# ControlBoard.net
KiCad netlist of a schematic drawn in EAGLE
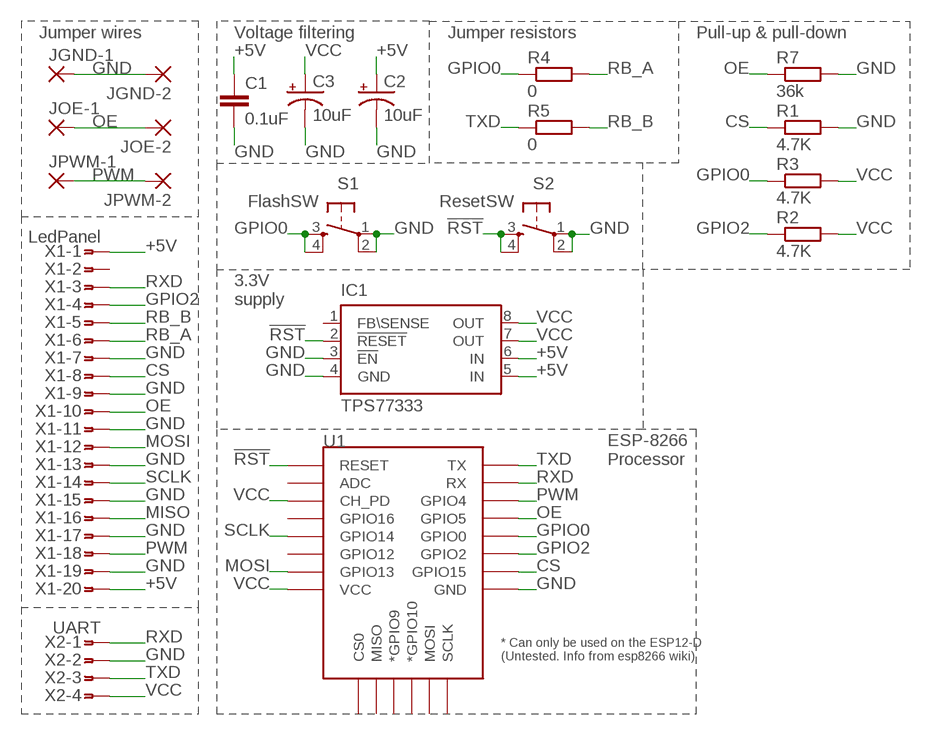
[diagram p0: schematic, sheet 1]

(export (version "E")
  (design (tool "Eeschema 10.0.6"))
  (components
    (comp (ref "C1")
      (value "0.1uF")
      (footprint "eagle-import:0603-CAP")
      (libsource (lib "eagle-import") (part "0.1UF-25V(+80/-20%)(0603)"))
    )
    (comp (ref "C2")
      (value "10uF")
      (footprint "eagle-import:EIA3528")
      (libsource (lib "eagle-import") (part "10UF-20V-10%(TANT)"))
    )
    (comp (ref "C3")
      (value "10uF")
      (footprint "eagle-import:EIA3528")
      (libsource (lib "eagle-import") (part "10UF-20V-10%(TANT)"))
    )
    (comp (ref "IC1")
      (value "TPS77333")
      (footprint "eagle-import:SOP-08")
      (fields (field (name "MF") "TEXAS INSTRUMENTS") (field (name "MPN") "TPS77333DGK"))
      (libsource (lib "eagle-import") (part "TPS77333"))
    )
    (comp (ref "JGND-1")
      (value "SMD2")
      (footprint "eagle-import:SMD1,27-2,54")
      (libsource (lib "eagle-import") (part "SMD2"))
    )
    (comp (ref "JGND-2")
      (value "SMD2")
      (footprint "eagle-import:SMD1,27-2,54")
      (libsource (lib "eagle-import") (part "SMD2"))
    )
    (comp (ref "JOE-1")
      (value "SMD2")
      (footprint "eagle-import:SMD1,27-2,54")
      (libsource (lib "eagle-import") (part "SMD2"))
    )
    (comp (ref "JOE-2")
      (value "SMD2")
      (footprint "eagle-import:SMD1,27-2,54")
      (libsource (lib "eagle-import") (part "SMD2"))
    )
    (comp (ref "JPWM-1")
      (value "SMD2")
      (footprint "eagle-import:SMD1,27-2,54")
      (libsource (lib "eagle-import") (part "SMD2"))
    )
    (comp (ref "JPWM-2")
      (value "SMD2")
      (footprint "eagle-import:SMD1,27-2,54")
      (libsource (lib "eagle-import") (part "SMD2"))
    )
    (comp (ref "R1")
      (value "4.7K")
      (footprint "eagle-import:R1206")
      (libsource (lib "eagle-import") (part "R-EU_R1206"))
    )
    (comp (ref "R2")
      (value "4.7K")
      (footprint "eagle-import:R1206")
      (libsource (lib "eagle-import") (part "R-EU_R1206"))
    )
    (comp (ref "R3")
      (value "4.7K")
      (footprint "eagle-import:R1206")
      (libsource (lib "eagle-import") (part "R-EU_R1206"))
    )
    (comp (ref "R4")
      (value "0")
      (footprint "eagle-import:R5025W")
      (libsource (lib "eagle-import") (part "R-EU_R5025W"))
    )
    (comp (ref "R5")
      (value "0")
      (footprint "eagle-import:R5025W")
      (libsource (lib "eagle-import") (part "R-EU_R5025W"))
    )
    (comp (ref "R7")
      (value "36k")
      (footprint "eagle-import:M2012")
      (libsource (lib "eagle-import") (part "R-EU_M2012"))
    )
    (comp (ref "S1")
      (value "FlashSW")
      (footprint "eagle-import:DTSM-6")
      (libsource (lib "eagle-import") (part "DTSM-6"))
    )
    (comp (ref "S2")
      (value "ResetSW")
      (footprint "eagle-import:DTSM-6")
      (libsource (lib "eagle-import") (part "DTSM-6"))
    )
    (comp (ref "U1")
      (value "ESP12ESMD")
      (footprint "eagle-import:ESP12E-SMD")
      (libsource (lib "eagle-import") (part "ESP12ESMD"))
    )
    (comp (ref "X1")
      (value "LedPanel")
      (footprint "eagle-import:SMDTOP20")
      (libsource (lib "eagle-import") (part "SMDTOP-20"))
    )
    (comp (ref "X2")
      (value "UART")
      (footprint "eagle-import:SMDTOP4")
      (libsource (lib "eagle-import") (part "SMDTOP-4"))
    )
  )
  (nets
    (net (code "1") (name "/+5V") (class "Default")
      (node (ref "C1") (pin "1") (pinfunction "1_1") (pintype "passive"))
      (node (ref "C2") (pin "A") (pinfunction "+_A") (pintype "passive"))
      (node (ref "IC1") (pin "5") (pinfunction "IN_5") (pintype "input"))
      (node (ref "IC1") (pin "6") (pinfunction "IN_6") (pintype "input"))
      (node (ref "X1") (pin "1") (pinfunction "1_1") (pintype "passive"))
      (node (ref "X1") (pin "20") (pinfunction "1_20") (pintype "passive"))
    )
    (net (code "2") (name "/CS") (class "Default")
      (node (ref "R1") (pin "1") (pinfunction "1_1") (pintype "passive"))
      (node (ref "U1") (pin "GPIO15") (pinfunction "GPIO15_GPIO15") (pintype "bidirectional"))
      (node (ref "X1") (pin "8") (pinfunction "1_8") (pintype "passive"))
    )
    (net (code "3") (name "/GND") (class "Default")
      (node (ref "C1") (pin "2") (pinfunction "2_2") (pintype "passive"))
      (node (ref "C2") (pin "C") (pinfunction "-_C") (pintype "passive"))
      (node (ref "C3") (pin "C") (pinfunction "-_C") (pintype "passive"))
      (node (ref "IC1") (pin "3") (pinfunction "~{EN}_3") (pintype "input"))
      (node (ref "IC1") (pin "4") (pinfunction "GND_4") (pintype "power_in"))
      (node (ref "JGND-1") (pin "1") (pinfunction "P_1") (pintype "passive"))
      (node (ref "JGND-2") (pin "1") (pinfunction "P_1") (pintype "passive"))
      (node (ref "R1") (pin "2") (pinfunction "2_2") (pintype "passive"))
      (node (ref "R7") (pin "2") (pinfunction "2_2") (pintype "passive"))
      (node (ref "S1") (pin "1") (pinfunction "1_1") (pintype "passive"))
      (node (ref "S1") (pin "2") (pinfunction "2_2") (pintype "passive"))
      (node (ref "S2") (pin "1") (pinfunction "1_1") (pintype "passive"))
      (node (ref "S2") (pin "2") (pinfunction "2_2") (pintype "passive"))
      (node (ref "U1") (pin "GND") (pinfunction "GND_GND") (pintype "bidirectional"))
      (node (ref "X1") (pin "11") (pinfunction "1_11") (pintype "passive"))
      (node (ref "X1") (pin "13") (pinfunction "1_13") (pintype "passive"))
      (node (ref "X1") (pin "15") (pinfunction "1_15") (pintype "passive"))
      (node (ref "X1") (pin "17") (pinfunction "1_17") (pintype "passive"))
      (node (ref "X1") (pin "19") (pinfunction "1_19") (pintype "passive"))
      (node (ref "X1") (pin "7") (pinfunction "1_7") (pintype "passive"))
      (node (ref "X1") (pin "9") (pinfunction "1_9") (pintype "passive"))
      (node (ref "X2") (pin "2") (pinfunction "1_2") (pintype "passive"))
    )
    (net (code "4") (name "/GPIO0") (class "Default")
      (node (ref "R3") (pin "1") (pinfunction "1_1") (pintype "passive"))
      (node (ref "R4") (pin "1") (pinfunction "1_1") (pintype "passive"))
      (node (ref "S1") (pin "3") (pinfunction "3_3") (pintype "passive"))
      (node (ref "S1") (pin "4") (pinfunction "4_4") (pintype "passive"))
      (node (ref "U1") (pin "GPIO0") (pinfunction "GPIO0_GPIO0") (pintype "bidirectional"))
    )
    (net (code "5") (name "/GPIO2") (class "Default")
      (node (ref "R2") (pin "1") (pinfunction "1_1") (pintype "passive"))
      (node (ref "U1") (pin "GPIO2") (pinfunction "GPIO2_GPIO2") (pintype "bidirectional"))
      (node (ref "X1") (pin "4") (pinfunction "1_4") (pintype "passive"))
    )
    (net (code "6") (name "/MISO") (class "Default")
      (node (ref "X1") (pin "16") (pinfunction "1_16") (pintype "passive"))
    )
    (net (code "7") (name "/MOSI") (class "Default")
      (node (ref "U1") (pin "GPIO13") (pinfunction "GPIO13_GPIO13") (pintype "bidirectional"))
      (node (ref "X1") (pin "12") (pinfunction "1_12") (pintype "passive"))
    )
    (net (code "8") (name "/OE") (class "Default")
      (node (ref "JOE-1") (pin "1") (pinfunction "P_1") (pintype "passive"))
      (node (ref "JOE-2") (pin "1") (pinfunction "P_1") (pintype "passive"))
      (node (ref "R7") (pin "1") (pinfunction "1_1") (pintype "passive"))
      (node (ref "U1") (pin "GPIO5") (pinfunction "GPIO5_GPIO5") (pintype "bidirectional"))
      (node (ref "X1") (pin "10") (pinfunction "1_10") (pintype "passive"))
    )
    (net (code "9") (name "/PWM") (class "Default")
      (node (ref "JPWM-1") (pin "1") (pinfunction "P_1") (pintype "passive"))
      (node (ref "JPWM-2") (pin "1") (pinfunction "P_1") (pintype "passive"))
      (node (ref "U1") (pin "GPIO4") (pinfunction "GPIO4_GPIO4") (pintype "bidirectional"))
      (node (ref "X1") (pin "18") (pinfunction "1_18") (pintype "passive"))
    )
    (net (code "10") (name "/RB_A") (class "Default")
      (node (ref "R4") (pin "2") (pinfunction "2_2") (pintype "passive"))
      (node (ref "X1") (pin "6") (pinfunction "1_6") (pintype "passive"))
    )
    (net (code "11") (name "/RB_B") (class "Default")
      (node (ref "R5") (pin "2") (pinfunction "2_2") (pintype "passive"))
      (node (ref "X1") (pin "5") (pinfunction "1_5") (pintype "passive"))
    )
    (net (code "12") (name "/RXD") (class "Default")
      (node (ref "U1") (pin "RXD0") (pinfunction "RX_RXD0") (pintype "bidirectional"))
      (node (ref "X1") (pin "3") (pinfunction "1_3") (pintype "passive"))
      (node (ref "X2") (pin "1") (pinfunction "1_1") (pintype "passive"))
    )
    (net (code "13") (name "/SCLK") (class "Default")
      (node (ref "U1") (pin "GPIO14") (pinfunction "GPIO14_GPIO14") (pintype "bidirectional"))
      (node (ref "X1") (pin "14") (pinfunction "1_14") (pintype "passive"))
    )
    (net (code "14") (name "/TXD") (class "Default")
      (node (ref "R5") (pin "1") (pinfunction "1_1") (pintype "passive"))
      (node (ref "U1") (pin "TXD0") (pinfunction "TX_TXD0") (pintype "bidirectional"))
      (node (ref "X2") (pin "3") (pinfunction "1_3") (pintype "passive"))
    )
    (net (code "15") (name "/VCC") (class "Default")
      (node (ref "C3") (pin "A") (pinfunction "+_A") (pintype "passive"))
      (node (ref "IC1") (pin "7") (pinfunction "OUT_7") (pintype "output"))
      (node (ref "IC1") (pin "8") (pinfunction "OUT_8") (pintype "passive"))
      (node (ref "R2") (pin "2") (pinfunction "2_2") (pintype "passive"))
      (node (ref "R3") (pin "2") (pinfunction "2_2") (pintype "passive"))
      (node (ref "U1") (pin "CH_PD") (pinfunction "CH_PD_CH_PD") (pintype "bidirectional"))
      (node (ref "U1") (pin "VCC") (pinfunction "VCC_VCC") (pintype "bidirectional"))
      (node (ref "X2") (pin "4") (pinfunction "1_4") (pintype "passive"))
    )
    (net (code "16") (name "/~{RST}") (class "Default")
      (node (ref "IC1") (pin "2") (pinfunction "~{RESET}_2") (pintype "input"))
      (node (ref "S2") (pin "3") (pinfunction "3_3") (pintype "passive"))
      (node (ref "S2") (pin "4") (pinfunction "4_4") (pintype "passive"))
      (node (ref "U1") (pin "RESET") (pinfunction "RESET_RESET") (pintype "bidirectional"))
    )
    (net (code "17") (name "unconnected-(IC1-FB\\SENSE-Pad1)") (class "Default")
      (node (ref "IC1") (pin "1") (pinfunction "FB\\SENSE_1") (pintype "input"))
    )
    (net (code "18") (name "unconnected-(U1-*GPIO9-PadGPIO9)") (class "Default")
      (node (ref "U1") (pin "GPIO9") (pinfunction "*GPIO9_GPIO9") (pintype "bidirectional"))
    )
    (net (code "19") (name "unconnected-(U1-*GPIO10-PadGPIO10)") (class "Default")
      (node (ref "U1") (pin "GPIO10") (pinfunction "*GPIO10_GPIO10") (pintype "bidirectional"))
    )
    (net (code "20") (name "unconnected-(U1-PadADC)") (class "Default")
      (node (ref "U1") (pin "ADC") (pinfunction "ADC_ADC") (pintype "bidirectional"))
    )
    (net (code "21") (name "unconnected-(U1-PadCS0)") (class "Default")
      (node (ref "U1") (pin "CS0") (pinfunction "CS0_CS0") (pintype "bidirectional"))
    )
    (net (code "22") (name "unconnected-(U1-PadGPIO12)") (class "Default")
      (node (ref "U1") (pin "GPIO12") (pinfunction "GPIO12_GPIO12") (pintype "bidirectional"))
    )
    (net (code "23") (name "unconnected-(U1-PadGPIO16)") (class "Default")
      (node (ref "U1") (pin "GPIO16") (pinfunction "GPIO16_GPIO16") (pintype "bidirectional"))
    )
    (net (code "24") (name "unconnected-(U1-PadMISO)") (class "Default")
      (node (ref "U1") (pin "MISO") (pinfunction "MISO_MISO") (pintype "bidirectional"))
    )
    (net (code "25") (name "unconnected-(U1-PadMOSI)") (class "Default")
      (node (ref "U1") (pin "MOSI") (pinfunction "MOSI_MOSI") (pintype "bidirectional"))
    )
    (net (code "26") (name "unconnected-(U1-PadSCLK)") (class "Default")
      (node (ref "U1") (pin "SCLK") (pinfunction "SCLK_SCLK") (pintype "bidirectional"))
    )
    (net (code "27") (name "unconnected-(X1L-1-Pad2)") (class "Default")
      (node (ref "X1") (pin "2") (pinfunction "1_2") (pintype "passive"))
    )
  )
)
